# Birthday_Badge.net
KiCad netlist of a schematic drawn in EAGLE
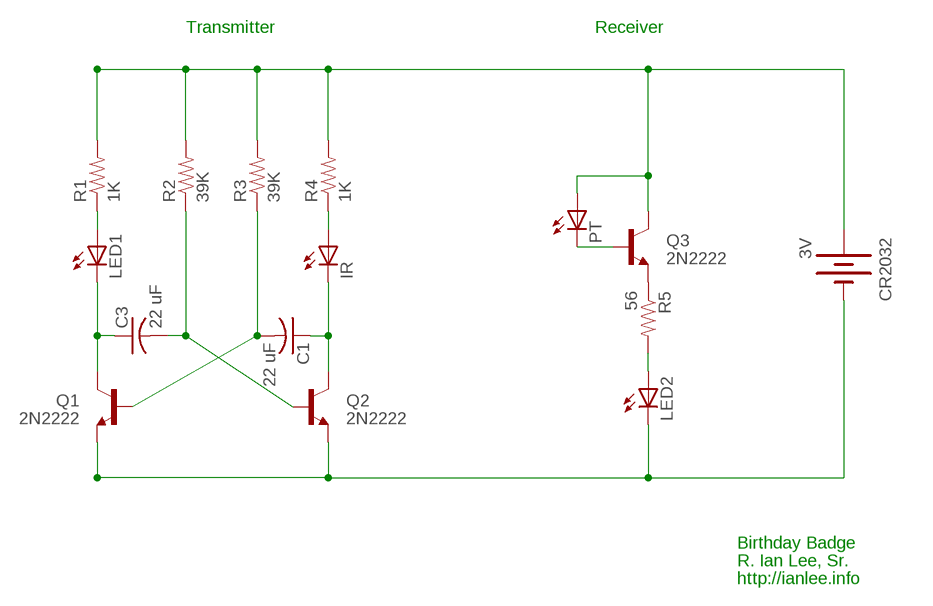
[diagram p0: schematic, sheet 1]

(export (version "E")
  (design (tool "Eeschema 10.0.6"))
  (components
    (comp (ref "C1")
      (value "22 uF")
      (footprint "eagle-import:C1210K")
      (libsource (lib "eagle-import") (part "C-USC1210K"))
    )
    (comp (ref "C3")
      (value "22 uF")
      (footprint "eagle-import:C1210K")
      (libsource (lib "eagle-import") (part "C-USC1210K"))
    )
    (comp (ref "CR2032")
      (value "3V")
      (footprint "eagle-import:BATTCON_20MM")
      (libsource (lib "eagle-import") (part "BATTERY20SMD"))
    )
    (comp (ref "IR")
      (value "LED5MM")
      (footprint "eagle-import:LED5MM")
      (libsource (lib "eagle-import") (part "LED5MM"))
    )
    (comp (ref "LED1")
      (value "LED5MM")
      (footprint "eagle-import:LED5MM")
      (libsource (lib "eagle-import") (part "LED5MM"))
    )
    (comp (ref "LED2")
      (value "LED5MM")
      (footprint "eagle-import:LED5MM")
      (libsource (lib "eagle-import") (part "LED5MM"))
    )
    (comp (ref "PT")
      (value "LED5MM")
      (footprint "eagle-import:LED5MM")
      (libsource (lib "eagle-import") (part "LED5MM"))
    )
    (comp (ref "Q1")
      (value "2N2222")
      (footprint "eagle-import:TO-92-AMMO")
      (libsource (lib "eagle-import") (part "TRANSISTOR_NPNTO-92-AMMO"))
    )
    (comp (ref "Q2")
      (value "2N2222")
      (footprint "eagle-import:TO-92-AMMO")
      (libsource (lib "eagle-import") (part "TRANSISTOR_NPNTO-92-AMMO"))
    )
    (comp (ref "Q3")
      (value "2N2222")
      (footprint "eagle-import:TO-92-AMMO")
      (libsource (lib "eagle-import") (part "TRANSISTOR_NPNTO-92-AMMO"))
    )
    (comp (ref "R1")
      (value "1K")
      (footprint "eagle-import:AXIAL-0.4")
      (libsource (lib "eagle-import") (part "RESISTORPTH-1/4W"))
    )
    (comp (ref "R2")
      (value "39K")
      (footprint "eagle-import:AXIAL-0.4")
      (libsource (lib "eagle-import") (part "RESISTORPTH-1/4W"))
    )
    (comp (ref "R3")
      (value "39K")
      (footprint "eagle-import:AXIAL-0.4")
      (libsource (lib "eagle-import") (part "RESISTORPTH-1/4W"))
    )
    (comp (ref "R4")
      (value "1K")
      (footprint "eagle-import:AXIAL-0.4")
      (libsource (lib "eagle-import") (part "RESISTORPTH-1/4W"))
    )
    (comp (ref "R5")
      (value "56")
      (footprint "eagle-import:AXIAL-0.4")
      (libsource (lib "eagle-import") (part "RESISTORPTH-1/4W"))
    )
  )
  (nets
    (net (code "1") (name "Net-(CR2032-+)") (class "Default")
      (node (ref "CR2032") (pin "1") (pinfunction "+_1") (pintype "power_in"))
      (node (ref "PT") (pin "A") (pinfunction "A_A") (pintype "passive"))
      (node (ref "Q3") (pin "3") (pinfunction "C_3") (pintype "passive"))
      (node (ref "R1") (pin "P$2") (pinfunction "2_P$2") (pintype "passive"))
      (node (ref "R2") (pin "P$2") (pinfunction "2_P$2") (pintype "passive"))
      (node (ref "R3") (pin "P$2") (pinfunction "2_P$2") (pintype "passive"))
      (node (ref "R4") (pin "P$2") (pinfunction "2_P$2") (pintype "passive"))
    )
    (net (code "2") (name "Net-(CR2032--)") (class "Default")
      (node (ref "CR2032") (pin "2") (pinfunction "-_2") (pintype "power_in"))
      (node (ref "LED2") (pin "K") (pinfunction "C_K") (pintype "passive"))
      (node (ref "Q1") (pin "1") (pinfunction "E_1") (pintype "passive"))
      (node (ref "Q2") (pin "1") (pinfunction "E_1") (pintype "passive"))
    )
    (net (code "3") (name "Net-(IR-C)") (class "Default")
      (node (ref "C1") (pin "1") (pinfunction "1_1") (pintype "passive"))
      (node (ref "IR") (pin "K") (pinfunction "C_K") (pintype "passive"))
      (node (ref "Q2") (pin "3") (pinfunction "C_3") (pintype "passive"))
    )
    (net (code "4") (name "Net-(LED1-C)") (class "Default")
      (node (ref "C3") (pin "1") (pinfunction "1_1") (pintype "passive"))
      (node (ref "LED1") (pin "K") (pinfunction "C_K") (pintype "passive"))
      (node (ref "Q1") (pin "3") (pinfunction "C_3") (pintype "passive"))
    )
    (net (code "5") (name "Net-(PT-C)") (class "Default")
      (node (ref "PT") (pin "K") (pinfunction "C_K") (pintype "passive"))
      (node (ref "Q3") (pin "2") (pinfunction "B_2") (pintype "passive"))
    )
    (net (code "6") (name "Net-(Q1-B)") (class "Default")
      (node (ref "C1") (pin "2") (pinfunction "2_2") (pintype "passive"))
      (node (ref "Q1") (pin "2") (pinfunction "B_2") (pintype "passive"))
      (node (ref "R3") (pin "P$1") (pinfunction "1_P$1") (pintype "passive"))
    )
    (net (code "7") (name "Net-(Q2-B)") (class "Default")
      (node (ref "C3") (pin "2") (pinfunction "2_2") (pintype "passive"))
      (node (ref "Q2") (pin "2") (pinfunction "B_2") (pintype "passive"))
      (node (ref "R2") (pin "P$1") (pinfunction "1_P$1") (pintype "passive"))
    )
    (net (code "8") (name "Net-(Q3-E)") (class "Default")
      (node (ref "Q3") (pin "1") (pinfunction "E_1") (pintype "passive"))
      (node (ref "R5") (pin "P$1") (pinfunction "1_P$1") (pintype "passive"))
    )
    (net (code "9") (name "Net-(R1-1)") (class "Default")
      (node (ref "LED1") (pin "A") (pinfunction "A_A") (pintype "passive"))
      (node (ref "R1") (pin "P$1") (pinfunction "1_P$1") (pintype "passive"))
    )
    (net (code "10") (name "Net-(R4-1)") (class "Default")
      (node (ref "IR") (pin "A") (pinfunction "A_A") (pintype "passive"))
      (node (ref "R4") (pin "P$1") (pinfunction "1_P$1") (pintype "passive"))
    )
    (net (code "11") (name "Net-(R5-2)") (class "Default")
      (node (ref "LED2") (pin "A") (pinfunction "A_A") (pintype "passive"))
      (node (ref "R5") (pin "P$2") (pinfunction "2_P$2") (pintype "passive"))
    )
  )
)
